# Door.net
KiCad netlist of a schematic drawn in EAGLE
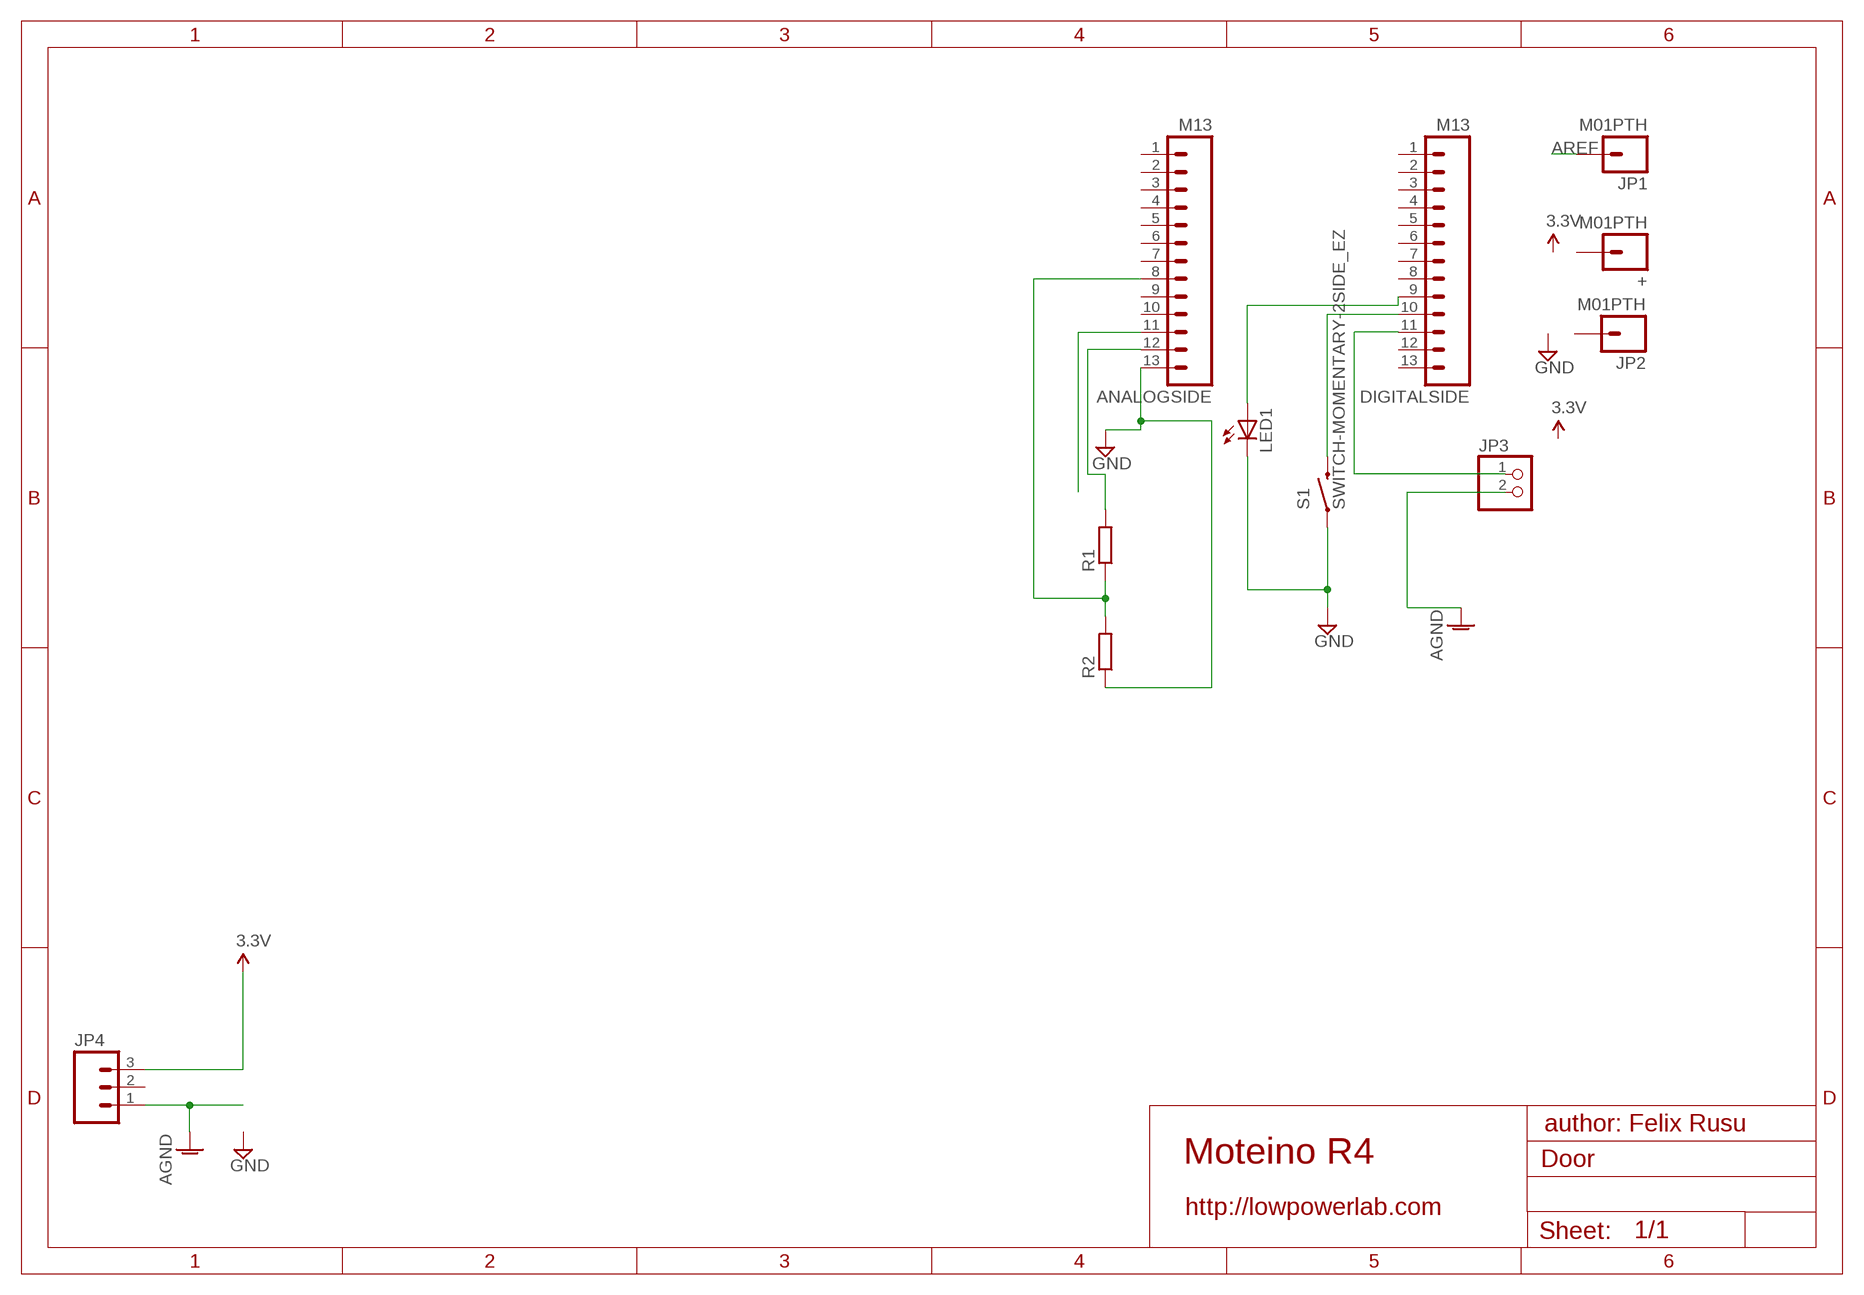
[diagram p0: schematic, sheet 1]

(export (version "E")
  (design (tool "Eeschema 10.0.6"))
  (components
    (comp (ref "+")
      (value "M01PTH")
      (footprint "eagle-import:1X01")
      (libsource (lib "eagle-import") (part "M01PTH"))
    )
    (comp (ref "ANALOGSIDE")
      (value "M13")
      (footprint "eagle-import:1X13")
      (libsource (lib "eagle-import") (part "M13"))
    )
    (comp (ref "DIGITALSIDE")
      (value "M13")
      (footprint "eagle-import:1X13")
      (libsource (lib "eagle-import") (part "M13"))
    )
    (comp (ref "JP1")
      (value "M01PTH")
      (footprint "eagle-import:1X01")
      (libsource (lib "eagle-import") (part "M01PTH"))
    )
    (comp (ref "JP2")
      (value "M01PTH")
      (footprint "eagle-import:1X01")
      (libsource (lib "eagle-import") (part "M01PTH"))
    )
    (comp (ref "JP3")
      (value "PINHD-1X2")
      (footprint "eagle-import:1X02")
      (libsource (lib "eagle-import") (part "PINHD-1X2"))
    )
    (comp (ref "JP4")
      (value "M03PTH")
      (footprint "eagle-import:1X03")
      (libsource (lib "eagle-import") (part "M03PTH"))
    )
    (comp (ref "LED1")
      (value "LED3MM")
      (footprint "eagle-import:LED3MM")
      (libsource (lib "eagle-import") (part "LED3MM"))
    )
    (comp (ref "R1")
      (value "R-EU_0204/7")
      (footprint "eagle-import:0204_7")
      (libsource (lib "eagle-import") (part "R-EU_0204/7"))
    )
    (comp (ref "R2")
      (value "R-EU_0204/7")
      (footprint "eagle-import:0204_7")
      (libsource (lib "eagle-import") (part "R-EU_0204/7"))
    )
    (comp (ref "S1")
      (value "SWITCH-MOMENTARY-2SIDE_EZ")
      (footprint "eagle-import:TACTILE-PTH-SIDEEZ")
      (libsource (lib "eagle-import") (part "SWITCH-MOMENTARY-2SIDE_EZ"))
    )
  )
  (nets
    (net (code "1") (name "/AREF") (class "Default")
      (node (ref "JP1") (pin "1") (pinfunction "1_1") (pintype "passive"))
    )
    (net (code "2") (name "3.3V") (class "Default")
      (node (ref "JP4") (pin "3") (pinfunction "3_3") (pintype "passive"))
    )
    (net (code "3") (name "AGND") (class "Default")
      (node (ref "JP3") (pin "2") (pinfunction "2_2") (pintype "passive"))
      (node (ref "JP4") (pin "1") (pinfunction "1_1") (pintype "passive"))
    )
    (net (code "4") (name "GND") (class "Default")
      (node (ref "ANALOGSIDE") (pin "13") (pinfunction "13_13") (pintype "passive"))
      (node (ref "LED1") (pin "K") (pinfunction "C_K") (pintype "passive"))
      (node (ref "R2") (pin "1") (pinfunction "1_1") (pintype "passive"))
      (node (ref "S1") (pin "1") (pinfunction "1_1") (pintype "passive"))
    )
    (net (code "5") (name "Net-(ANALOGSIDE-Pad8)") (class "Default")
      (node (ref "ANALOGSIDE") (pin "8") (pinfunction "8_8") (pintype "passive"))
      (node (ref "R1") (pin "1") (pinfunction "1_1") (pintype "passive"))
      (node (ref "R2") (pin "2") (pinfunction "2_2") (pintype "passive"))
    )
    (net (code "6") (name "Net-(ANALOGSIDE-Pad12)") (class "Default")
      (node (ref "ANALOGSIDE") (pin "12") (pinfunction "12_12") (pintype "passive"))
      (node (ref "R1") (pin "2") (pinfunction "2_2") (pintype "passive"))
    )
    (net (code "7") (name "Net-(DIGITALSIDE-Pad9)") (class "Default")
      (node (ref "DIGITALSIDE") (pin "9") (pinfunction "9_9") (pintype "passive"))
      (node (ref "LED1") (pin "A") (pinfunction "A_A") (pintype "passive"))
    )
    (net (code "8") (name "Net-(DIGITALSIDE-Pad10)") (class "Default")
      (node (ref "DIGITALSIDE") (pin "10") (pinfunction "10_10") (pintype "passive"))
      (node (ref "S1") (pin "2") (pinfunction "2_2") (pintype "passive"))
    )
    (net (code "9") (name "Net-(DIGITALSIDE-Pad11)") (class "Default")
      (node (ref "DIGITALSIDE") (pin "11") (pinfunction "11_11") (pintype "passive"))
      (node (ref "JP3") (pin "1") (pinfunction "1_1") (pintype "passive"))
    )
    (net (code "10") (name "unconnected-(+-Pad1)") (class "Default")
      (node (ref "+") (pin "1") (pinfunction "1_1") (pintype "passive"))
    )
    (net (code "11") (name "unconnected-(ANALOGSIDE-Pad1)") (class "Default")
      (node (ref "ANALOGSIDE") (pin "1") (pinfunction "1_1") (pintype "passive"))
    )
    (net (code "12") (name "unconnected-(ANALOGSIDE-Pad2)") (class "Default")
      (node (ref "ANALOGSIDE") (pin "2") (pinfunction "2_2") (pintype "passive"))
    )
    (net (code "13") (name "unconnected-(ANALOGSIDE-Pad3)") (class "Default")
      (node (ref "ANALOGSIDE") (pin "3") (pinfunction "3_3") (pintype "passive"))
    )
    (net (code "14") (name "unconnected-(ANALOGSIDE-Pad4)") (class "Default")
      (node (ref "ANALOGSIDE") (pin "4") (pinfunction "4_4") (pintype "passive"))
    )
    (net (code "15") (name "unconnected-(ANALOGSIDE-Pad5)") (class "Default")
      (node (ref "ANALOGSIDE") (pin "5") (pinfunction "5_5") (pintype "passive"))
    )
    (net (code "16") (name "unconnected-(ANALOGSIDE-Pad6)") (class "Default")
      (node (ref "ANALOGSIDE") (pin "6") (pinfunction "6_6") (pintype "passive"))
    )
    (net (code "17") (name "unconnected-(ANALOGSIDE-Pad7)") (class "Default")
      (node (ref "ANALOGSIDE") (pin "7") (pinfunction "7_7") (pintype "passive"))
    )
    (net (code "18") (name "unconnected-(ANALOGSIDE-Pad9)") (class "Default")
      (node (ref "ANALOGSIDE") (pin "9") (pinfunction "9_9") (pintype "passive"))
    )
    (net (code "19") (name "unconnected-(ANALOGSIDE-Pad10)") (class "Default")
      (node (ref "ANALOGSIDE") (pin "10") (pinfunction "10_10") (pintype "passive"))
    )
    (net (code "20") (name "unconnected-(ANALOGSIDE-Pad11)") (class "Default")
      (node (ref "ANALOGSIDE") (pin "11") (pinfunction "11_11") (pintype "passive"))
    )
    (net (code "21") (name "unconnected-(DIGITALSIDE-Pad1)") (class "Default")
      (node (ref "DIGITALSIDE") (pin "1") (pinfunction "1_1") (pintype "passive"))
    )
    (net (code "22") (name "unconnected-(DIGITALSIDE-Pad2)") (class "Default")
      (node (ref "DIGITALSIDE") (pin "2") (pinfunction "2_2") (pintype "passive"))
    )
    (net (code "23") (name "unconnected-(DIGITALSIDE-Pad3)") (class "Default")
      (node (ref "DIGITALSIDE") (pin "3") (pinfunction "3_3") (pintype "passive"))
    )
    (net (code "24") (name "unconnected-(DIGITALSIDE-Pad4)") (class "Default")
      (node (ref "DIGITALSIDE") (pin "4") (pinfunction "4_4") (pintype "passive"))
    )
    (net (code "25") (name "unconnected-(DIGITALSIDE-Pad5)") (class "Default")
      (node (ref "DIGITALSIDE") (pin "5") (pinfunction "5_5") (pintype "passive"))
    )
    (net (code "26") (name "unconnected-(DIGITALSIDE-Pad6)") (class "Default")
      (node (ref "DIGITALSIDE") (pin "6") (pinfunction "6_6") (pintype "passive"))
    )
    (net (code "27") (name "unconnected-(DIGITALSIDE-Pad7)") (class "Default")
      (node (ref "DIGITALSIDE") (pin "7") (pinfunction "7_7") (pintype "passive"))
    )
    (net (code "28") (name "unconnected-(DIGITALSIDE-Pad8)") (class "Default")
      (node (ref "DIGITALSIDE") (pin "8") (pinfunction "8_8") (pintype "passive"))
    )
    (net (code "29") (name "unconnected-(DIGITALSIDE-Pad12)") (class "Default")
      (node (ref "DIGITALSIDE") (pin "12") (pinfunction "12_12") (pintype "passive"))
    )
    (net (code "30") (name "unconnected-(DIGITALSIDE-Pad13)") (class "Default")
      (node (ref "DIGITALSIDE") (pin "13") (pinfunction "13_13") (pintype "passive"))
    )
    (net (code "31") (name "unconnected-(JP2-Pad1)") (class "Default")
      (node (ref "JP2") (pin "1") (pinfunction "1_1") (pintype "passive"))
    )
    (net (code "32") (name "unconnected-(JP4-Pad2)") (class "Default")
      (node (ref "JP4") (pin "2") (pinfunction "2_2") (pintype "passive"))
    )
  )
)
